# SANE_v2.net
KiCad netlist of a schematic drawn in EAGLE
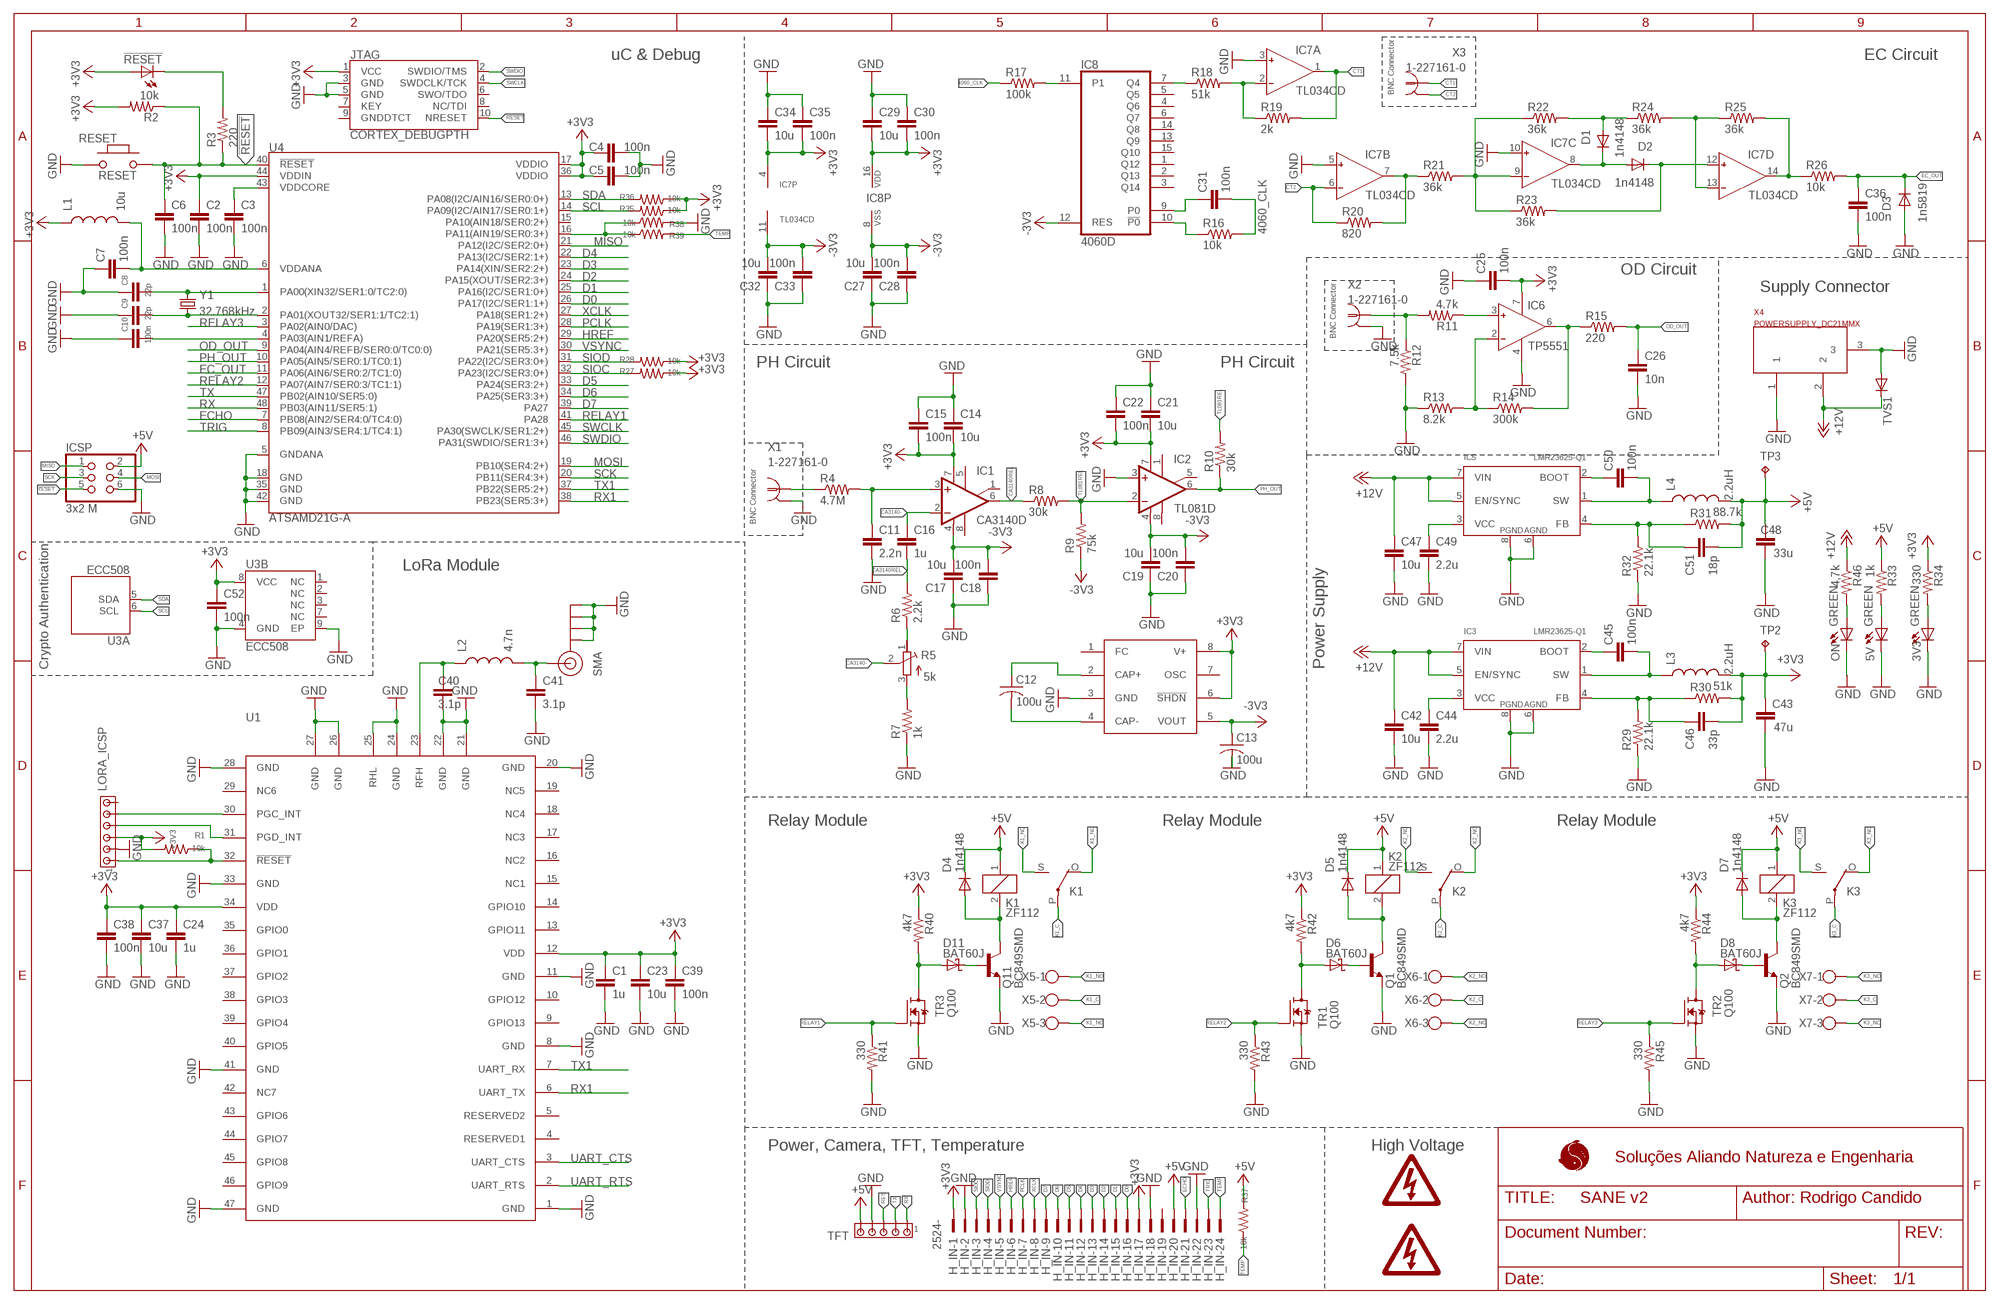
[diagram p0: schematic, sheet 1]

(export (version "E")
  (design (tool "Eeschema 10.0.6"))
  (components
    (comp (ref "!RESET")
      (value "LEDCHIPLED_0805")
      (footprint "eagle-import:CHIPLED_0805")
      (libsource (lib "eagle-import") (part "LEDCHIPLED_0805"))
    )
    (comp (ref "3V3")
      (value "GREEN")
      (footprint "eagle-import:CHIP-LED0805")
      (libsource (lib "eagle-import") (part "LEDCHIP-LED0805"))
    )
    (comp (ref "5V")
      (value "GREEN")
      (footprint "eagle-import:CHIP-LED0805")
      (libsource (lib "eagle-import") (part "LEDCHIP-LED0805"))
    )
    (comp (ref "C1")
      (value "1u")
      (footprint "eagle-import:C1206")
      (libsource (lib "eagle-import") (part "C-EUC1206"))
    )
    (comp (ref "C2")
      (value "100n")
      (footprint "eagle-import:C0805")
      (libsource (lib "eagle-import") (part "C-EUC0805"))
    )
    (comp (ref "C3")
      (value "100n")
      (footprint "eagle-import:C0805")
      (libsource (lib "eagle-import") (part "C-EUC0805"))
    )
    (comp (ref "C4")
      (value "100n")
      (footprint "eagle-import:C0805")
      (libsource (lib "eagle-import") (part "C-EUC0805"))
    )
    (comp (ref "C5")
      (value "100n")
      (footprint "eagle-import:C0805")
      (libsource (lib "eagle-import") (part "C-EUC0805"))
    )
    (comp (ref "C6")
      (value "100n")
      (footprint "eagle-import:C0805")
      (libsource (lib "eagle-import") (part "C-EUC0805"))
    )
    (comp (ref "C7")
      (value "100n")
      (footprint "eagle-import:C0805")
      (libsource (lib "eagle-import") (part "C-EUC0805"))
    )
    (comp (ref "C8")
      (value "22p")
      (footprint "eagle-import:C0805")
      (libsource (lib "eagle-import") (part "C-EUC0805"))
    )
    (comp (ref "C9")
      (value "22p")
      (footprint "eagle-import:C0805")
      (libsource (lib "eagle-import") (part "C-EUC0805"))
    )
    (comp (ref "C10")
      (value "100n")
      (footprint "eagle-import:C0805")
      (libsource (lib "eagle-import") (part "C-EUC0805"))
    )
    (comp (ref "C11")
      (value "2.2n")
      (footprint "eagle-import:C0805")
      (libsource (lib "eagle-import") (part "C-EUC0805"))
    )
    (comp (ref "C12")
      (value "100u")
      (footprint "eagle-import:C1206")
      (libsource (lib "eagle-import") (part "C-USC1206"))
    )
    (comp (ref "C13")
      (value "100u")
      (footprint "eagle-import:C1206")
      (libsource (lib "eagle-import") (part "C-USC1206"))
    )
    (comp (ref "C14")
      (value "10u")
      (footprint "eagle-import:C1206")
      (libsource (lib "eagle-import") (part "C-EUC1206"))
    )
    (comp (ref "C15")
      (value "100n")
      (footprint "eagle-import:C0805")
      (libsource (lib "eagle-import") (part "C-EUC0805"))
    )
    (comp (ref "C16")
      (value "1u")
      (footprint "eagle-import:C1206")
      (libsource (lib "eagle-import") (part "C-EUC1206"))
    )
    (comp (ref "C17")
      (value "10u")
      (footprint "eagle-import:C1206")
      (libsource (lib "eagle-import") (part "C-EUC1206"))
    )
    (comp (ref "C18")
      (value "100n")
      (footprint "eagle-import:C0805")
      (libsource (lib "eagle-import") (part "C-EUC0805"))
    )
    (comp (ref "C19")
      (value "10u")
      (footprint "eagle-import:C1206")
      (libsource (lib "eagle-import") (part "C-EUC1206"))
    )
    (comp (ref "C20")
      (value "100n")
      (footprint "eagle-import:C0805")
      (libsource (lib "eagle-import") (part "C-EUC0805"))
    )
    (comp (ref "C21")
      (value "10u")
      (footprint "eagle-import:C1206")
      (libsource (lib "eagle-import") (part "C-EUC1206"))
    )
    (comp (ref "C22")
      (value "100n")
      (footprint "eagle-import:C0805")
      (libsource (lib "eagle-import") (part "C-EUC0805"))
    )
    (comp (ref "C23")
      (value "10u")
      (footprint "eagle-import:C1206")
      (libsource (lib "eagle-import") (part "C-EUC1206"))
    )
    (comp (ref "C24")
      (value "1u")
      (footprint "eagle-import:C1206")
      (libsource (lib "eagle-import") (part "C-EUC1206"))
    )
    (comp (ref "C25")
      (value "100n")
      (footprint "eagle-import:C0805")
      (libsource (lib "eagle-import") (part "C-EUC0805"))
    )
    (comp (ref "C26")
      (value "10n")
      (footprint "eagle-import:C0805")
      (libsource (lib "eagle-import") (part "C-EUC0805"))
    )
    (comp (ref "C27")
      (value "10u")
      (footprint "eagle-import:C1206")
      (libsource (lib "eagle-import") (part "C-EUC1206"))
    )
    (comp (ref "C28")
      (value "100n")
      (footprint "eagle-import:C0805")
      (libsource (lib "eagle-import") (part "C-EUC0805"))
    )
    (comp (ref "C29")
      (value "10u")
      (footprint "eagle-import:C1206")
      (libsource (lib "eagle-import") (part "C-EUC1206"))
    )
    (comp (ref "C30")
      (value "100n")
      (footprint "eagle-import:C0805")
      (libsource (lib "eagle-import") (part "C-EUC0805"))
    )
    (comp (ref "C31")
      (value "100n")
      (footprint "eagle-import:C0805")
      (libsource (lib "eagle-import") (part "C-EUC0805"))
    )
    (comp (ref "C32")
      (value "10u")
      (footprint "eagle-import:C1206")
      (libsource (lib "eagle-import") (part "C-EUC1206"))
    )
    (comp (ref "C33")
      (value "100n")
      (footprint "eagle-import:C0805")
      (libsource (lib "eagle-import") (part "C-EUC0805"))
    )
    (comp (ref "C34")
      (value "10u")
      (footprint "eagle-import:C1206")
      (libsource (lib "eagle-import") (part "C-EUC1206"))
    )
    (comp (ref "C35")
      (value "100n")
      (footprint "eagle-import:C0805")
      (libsource (lib "eagle-import") (part "C-EUC0805"))
    )
    (comp (ref "C36")
      (value "100n")
      (footprint "eagle-import:C0805")
      (libsource (lib "eagle-import") (part "C-EUC0805"))
    )
    (comp (ref "C37")
      (value "10u")
      (footprint "eagle-import:C1206")
      (libsource (lib "eagle-import") (part "C-EUC1206"))
    )
    (comp (ref "C38")
      (value "100n")
      (footprint "eagle-import:C0805")
      (libsource (lib "eagle-import") (part "C-EUC0805"))
    )
    (comp (ref "C39")
      (value "100n")
      (footprint "eagle-import:C0805")
      (libsource (lib "eagle-import") (part "C-EUC0805"))
    )
    (comp (ref "C40")
      (value "3.1p")
      (footprint "eagle-import:C0603")
      (libsource (lib "eagle-import") (part "C-EUC0603"))
    )
    (comp (ref "C41")
      (value "3.1p")
      (footprint "eagle-import:C0603")
      (libsource (lib "eagle-import") (part "C-EUC0603"))
    )
    (comp (ref "C42")
      (value "10u")
      (footprint "eagle-import:C1206")
      (libsource (lib "eagle-import") (part "C-EUC1206"))
    )
    (comp (ref "C43")
      (value "47u")
      (footprint "eagle-import:C1206")
      (libsource (lib "eagle-import") (part "C-EUC1206"))
    )
    (comp (ref "C44")
      (value "2.2u")
      (footprint "eagle-import:C0805")
      (libsource (lib "eagle-import") (part "C-EUC0805"))
    )
    (comp (ref "C45")
      (value "100n")
      (footprint "eagle-import:C0805")
      (libsource (lib "eagle-import") (part "C-EUC0805"))
    )
    (comp (ref "C46")
      (value "33p")
      (footprint "eagle-import:C0805")
      (libsource (lib "eagle-import") (part "C-EUC0805"))
    )
    (comp (ref "C47")
      (value "10u")
      (footprint "eagle-import:C1206")
      (libsource (lib "eagle-import") (part "C-EUC1206"))
    )
    (comp (ref "C48")
      (value "33u")
      (footprint "eagle-import:C1206")
      (libsource (lib "eagle-import") (part "C-EUC1206"))
    )
    (comp (ref "C49")
      (value "2.2u")
      (footprint "eagle-import:C0805")
      (libsource (lib "eagle-import") (part "C-EUC0805"))
    )
    (comp (ref "C50")
      (value "100n")
      (footprint "eagle-import:C0805")
      (libsource (lib "eagle-import") (part "C-EUC0805"))
    )
    (comp (ref "C51")
      (value "18p")
      (footprint "eagle-import:C0805")
      (libsource (lib "eagle-import") (part "C-EUC0805"))
    )
    (comp (ref "C52")
      (value "100n")
      (footprint "eagle-import:C0805")
      (libsource (lib "eagle-import") (part "C-EUC0805"))
    )
    (comp (ref "D1")
      (value "1n4148")
      (footprint "eagle-import:SOD123")
      (libsource (lib "eagle-import") (part "DIODE-SOD123"))
    )
    (comp (ref "D2")
      (value "1n4148")
      (footprint "eagle-import:SOD123")
      (libsource (lib "eagle-import") (part "DIODE-SOD123"))
    )
    (comp (ref "D3")
      (value "1n5819")
      (footprint "eagle-import:SOD123")
      (libsource (lib "eagle-import") (part "DIODE-SOD123"))
    )
    (comp (ref "D4")
      (value "1n4148")
      (footprint "eagle-import:SOD123")
      (libsource (lib "eagle-import") (part "DIODE-SOD123"))
    )
    (comp (ref "D5")
      (value "1n4148")
      (footprint "eagle-import:SOD123")
      (libsource (lib "eagle-import") (part "DIODE-SOD123"))
    )
    (comp (ref "D6")
      (value "BAT60J")
      (footprint "eagle-import:SOD323_ST")
      (libsource (lib "eagle-import") (part "BAT60J"))
    )
    (comp (ref "D7")
      (value "1n4148")
      (footprint "eagle-import:SOD123")
      (libsource (lib "eagle-import") (part "DIODE-SOD123"))
    )
    (comp (ref "D8")
      (value "BAT60J")
      (footprint "eagle-import:SOD323_ST")
      (libsource (lib "eagle-import") (part "BAT60J"))
    )
    (comp (ref "D11")
      (value "BAT60J")
      (footprint "eagle-import:SOD323_ST")
      (libsource (lib "eagle-import") (part "BAT60J"))
    )
    (comp (ref "H_IN")
      (value "2524-")
      (footprint "eagle-import:PAK100_2500-24")
      (libsource (lib "eagle-import") (part "2524-"))
    )
    (comp (ref "IC1")
      (value "CA3140D")
      (footprint "eagle-import:SO08")
      (libsource (lib "eagle-import") (part "CA3140D"))
    )
    (comp (ref "IC2")
      (value "TL081D")
      (footprint "eagle-import:SO08")
      (libsource (lib "eagle-import") (part "TL081D"))
    )
    (comp (ref "IC3")
      (value "LMR23625-Q1")
      (footprint "eagle-import:SO08")
      (fields (field (name "MF") "Texas Instruments"))
      (libsource (lib "eagle-import") (part "LMR23625-Q1"))
    )
    (comp (ref "IC4")
      (value "TC1121COA")
      (footprint "eagle-import:SO8")
      (libsource (lib "eagle-import") (part "TC1121COA"))
    )
    (comp (ref "IC5")
      (value "LMR23625-Q1")
      (footprint "eagle-import:SO08")
      (fields (field (name "MF") "Texas Instruments"))
      (libsource (lib "eagle-import") (part "LMR23625-Q1"))
    )
    (comp (ref "IC6")
      (value "TP5551")
      (footprint "eagle-import:SO8")
      (libsource (lib "eagle-import") (part "TP5551"))
    )
    (comp (ref "IC7")
      (value "TL034CD")
      (footprint "eagle-import:SO14")
      (libsource (lib "eagle-import") (part "TL034CD"))
    )
    (comp (ref "IC8")
      (value "4060D")
      (footprint "eagle-import:SO16")
      (libsource (lib "eagle-import") (part "4060D"))
    )
    (comp (ref "ICSP")
      (value "3x2 M")
      (footprint "eagle-import:2X03")
      (libsource (lib "eagle-import") (part "ICSP"))
    )
    (comp (ref "JTAG")
      (value "CORTEX_DEBUGPTH")
      (footprint "eagle-import:2X5-PTH-1.27MM")
      (libsource (lib "eagle-import") (part "CORTEX_DEBUGPTH"))
    )
    (comp (ref "K1")
      (value "ZF112")
      (footprint "eagle-import:ZF112")
      (libsource (lib "eagle-import") (part "ZF112"))
    )
    (comp (ref "K2")
      (value "ZF112")
      (footprint "eagle-import:ZF112")
      (libsource (lib "eagle-import") (part "ZF112"))
    )
    (comp (ref "K3")
      (value "ZF112")
      (footprint "eagle-import:ZF112")
      (libsource (lib "eagle-import") (part "ZF112"))
    )
    (comp (ref "L1")
      (value "10u")
      (footprint "eagle-import:0603")
      (libsource (lib "eagle-import") (part "INDUCTOR0603"))
    )
    (comp (ref "L2")
      (value "4.7n")
      (footprint "eagle-import:0603")
      (libsource (lib "eagle-import") (part "INDUCTOR0603"))
    )
    (comp (ref "L3")
      (value "2.2uH")
      (footprint "eagle-import:L-NR3010")
      (libsource (lib "eagle-import") (part "L-NR3010"))
    )
    (comp (ref "L4")
      (value "2.2uH")
      (footprint "eagle-import:L-NR3010")
      (libsource (lib "eagle-import") (part "L-NR3010"))
    )
    (comp (ref "LORA_ICSP")
      (value "MTA06-100")
      (footprint "eagle-import:10X06MTA")
      (libsource (lib "eagle-import") (part "MTA06-100"))
    )
    (comp (ref "ON")
      (value "GREEN")
      (footprint "eagle-import:CHIP-LED0805")
      (libsource (lib "eagle-import") (part "LEDCHIP-LED0805"))
    )
    (comp (ref "Q1")
      (value "BC849SMD")
      (footprint "eagle-import:SOT23-BEC")
      (libsource (lib "eagle-import") (part "BC849SMD"))
    )
    (comp (ref "Q2")
      (value "BC849SMD")
      (footprint "eagle-import:SOT23-BEC")
      (libsource (lib "eagle-import") (part "BC849SMD"))
    )
    (comp (ref "Q11")
      (value "BC849SMD")
      (footprint "eagle-import:SOT23-BEC")
      (libsource (lib "eagle-import") (part "BC849SMD"))
    )
    (comp (ref "R1")
      (value "10k")
      (footprint "eagle-import:R0805")
      (libsource (lib "eagle-import") (part "R-US_R0805"))
    )
    (comp (ref "R2")
      (value "10k")
      (footprint "eagle-import:R0805")
      (libsource (lib "eagle-import") (part "R-US_R0805"))
    )
    (comp (ref "R3")
      (value "220")
      (footprint "eagle-import:R0805")
      (libsource (lib "eagle-import") (part "R-US_R0805"))
    )
    (comp (ref "R4")
      (value "4.7M")
      (footprint "eagle-import:R0805")
      (libsource (lib "eagle-import") (part "R-US_R0805"))
    )
    (comp (ref "R5")
      (value "5k")
      (footprint "eagle-import:RTRIMT93YA")
      (libsource (lib "eagle-import") (part "R-TRIMMT93YA"))
    )
    (comp (ref "R6")
      (value "2.2k")
      (footprint "eagle-import:R0805")
      (libsource (lib "eagle-import") (part "R-US_R0805"))
    )
    (comp (ref "R7")
      (value "1k")
      (footprint "eagle-import:R0805")
      (libsource (lib "eagle-import") (part "R-US_R0805"))
    )
    (comp (ref "R8")
      (value "30k")
      (footprint "eagle-import:R0805")
      (libsource (lib "eagle-import") (part "R-US_R0805"))
    )
    (comp (ref "R9")
      (value "75k")
      (footprint "eagle-import:R0805")
      (libsource (lib "eagle-import") (part "R-US_R0805"))
    )
    (comp (ref "R10")
      (value "30k")
      (footprint "eagle-import:R0805")
      (libsource (lib "eagle-import") (part "R-US_R0805"))
    )
    (comp (ref "R11")
      (value "4.7k")
      (footprint "eagle-import:R0805")
      (libsource (lib "eagle-import") (part "R-US_R0805"))
    )
    (comp (ref "R12")
      (value "7.5k")
      (footprint "eagle-import:R0805")
      (libsource (lib "eagle-import") (part "R-US_R0805"))
    )
    (comp (ref "R13")
      (value "8.2k")
      (footprint "eagle-import:R0805")
      (libsource (lib "eagle-import") (part "R-US_R0805"))
    )
    (comp (ref "R14")
      (value "300k")
      (footprint "eagle-import:R0805")
      (libsource (lib "eagle-import") (part "R-US_R0805"))
    )
    (comp (ref "R15")
      (value "220")
      (footprint "eagle-import:R0805")
      (libsource (lib "eagle-import") (part "R-US_R0805"))
    )
    (comp (ref "R16")
      (value "10k")
      (footprint "eagle-import:R0805")
      (libsource (lib "eagle-import") (part "R-US_R0805"))
    )
    (comp (ref "R17")
      (value "100k")
      (footprint "eagle-import:R0805")
      (libsource (lib "eagle-import") (part "R-US_R0805"))
    )
    (comp (ref "R18")
      (value "51k")
      (footprint "eagle-import:R0805")
      (libsource (lib "eagle-import") (part "R-US_R0805"))
    )
    (comp (ref "R19")
      (value "2k")
      (footprint "eagle-import:R0805")
      (libsource (lib "eagle-import") (part "R-US_R0805"))
    )
    (comp (ref "R20")
      (value "820")
      (footprint "eagle-import:R0805")
      (libsource (lib "eagle-import") (part "R-US_R0805"))
    )
    (comp (ref "R21")
      (value "36k")
      (footprint "eagle-import:R0805")
      (libsource (lib "eagle-import") (part "R-US_R0805"))
    )
    (comp (ref "R22")
      (value "36k")
      (footprint "eagle-import:R0805")
      (libsource (lib "eagle-import") (part "R-US_R0805"))
    )
    (comp (ref "R23")
      (value "36k")
      (footprint "eagle-import:R0805")
      (libsource (lib "eagle-import") (part "R-US_R0805"))
    )
    (comp (ref "R24")
      (value "36k")
      (footprint "eagle-import:R0805")
      (libsource (lib "eagle-import") (part "R-US_R0805"))
    )
    (comp (ref "R25")
      (value "36k")
      (footprint "eagle-import:R0805")
      (libsource (lib "eagle-import") (part "R-US_R0805"))
    )
    (comp (ref "R26")
      (value "10k")
      (footprint "eagle-import:R0805")
      (libsource (lib "eagle-import") (part "R-US_R0805"))
    )
    (comp (ref "R27")
      (value "10k")
      (footprint "eagle-import:R0805")
      (libsource (lib "eagle-import") (part "R-US_R0805"))
    )
    (comp (ref "R28")
      (value "10k")
      (footprint "eagle-import:R0805")
      (libsource (lib "eagle-import") (part "R-US_R0805"))
    )
    (comp (ref "R29")
      (value "22.1k")
      (footprint "eagle-import:R0603")
      (libsource (lib "eagle-import") (part "R-US_R0603"))
    )
    (comp (ref "R30")
      (value "51k")
      (footprint "eagle-import:R0603")
      (libsource (lib "eagle-import") (part "R-US_R0603"))
    )
    (comp (ref "R31")
      (value "88.7k")
      (footprint "eagle-import:R0603")
      (libsource (lib "eagle-import") (part "R-US_R0603"))
    )
    (comp (ref "R32")
      (value "22.1k")
      (footprint "eagle-import:R0603")
      (libsource (lib "eagle-import") (part "R-US_R0603"))
    )
    (comp (ref "R33")
      (value "1k")
      (footprint "eagle-import:R0805")
      (libsource (lib "eagle-import") (part "resistor_R-US_R0805"))
    )
    (comp (ref "R34")
      (value "330")
      (footprint "eagle-import:R0805")
      (libsource (lib "eagle-import") (part "resistor_R-US_R0805"))
    )
    (comp (ref "R35")
      (value "10k")
      (footprint "eagle-import:R0805")
      (libsource (lib "eagle-import") (part "R-US_R0805"))
    )
    (comp (ref "R36")
      (value "10k")
      (footprint "eagle-import:R0805")
      (libsource (lib "eagle-import") (part "R-US_R0805"))
    )
    (comp (ref "R37")
      (value "10k")
      (footprint "eagle-import:R0805")
      (libsource (lib "eagle-import") (part "R-US_R0805"))
    )
    (comp (ref "R38")
      (value "10k")
      (footprint "eagle-import:R0805")
      (libsource (lib "eagle-import") (part "R-US_R0805"))
    )
    (comp (ref "R39")
      (value "10k")
      (footprint "eagle-import:R0805")
      (libsource (lib "eagle-import") (part "R-US_R0805"))
    )
    (comp (ref "R40")
      (value "4k7")
      (footprint "eagle-import:R0805")
      (libsource (lib "eagle-import") (part "R-US_R0805"))
    )
    (comp (ref "R41")
      (value "330")
      (footprint "eagle-import:R0805")
      (libsource (lib "eagle-import") (part "R-US_R0805"))
    )
    (comp (ref "R42")
      (value "4k7")
      (footprint "eagle-import:R0805")
      (libsource (lib "eagle-import") (part "R-US_R0805"))
    )
    (comp (ref "R43")
      (value "330")
      (footprint "eagle-import:R0805")
      (libsource (lib "eagle-import") (part "R-US_R0805"))
    )
    (comp (ref "R44")
      (value "4k7")
      (footprint "eagle-import:R0805")
      (libsource (lib "eagle-import") (part "R-US_R0805"))
    )
    (comp (ref "R45")
      (value "330")
      (footprint "eagle-import:R0805")
      (libsource (lib "eagle-import") (part "R-US_R0805"))
    )
    (comp (ref "R46")
      (value "4,7k")
      (footprint "eagle-import:R0805")
      (libsource (lib "eagle-import") (part "resistor_R-US_R0805"))
    )
    (comp (ref "RESET")
      (value "RESET")
      (footprint "eagle-import:SMD_157SW")
      (fields (field (name "PART_NUMBER") "IT-1185AP1C-160G-G_T&R"))
      (libsource (lib "eagle-import") (part "0173_IT-1185AP1C-160G-G_T&R"))
    )
    (comp (ref "SMA_GPS")
      (value "SMA_EDGE")
      (footprint "eagle-import:SMA-EDGE")
      (libsource (lib "eagle-import") (part "SMA_EDGE"))
    )
    (comp (ref "TFT")
      (value "MTA05-100")
      (footprint "eagle-import:10X05MTA")
      (libsource (lib "eagle-import") (part "MTA05-100"))
    )
    (comp (ref "TP2")
      (value "TPPAD1-13")
      (footprint "eagle-import:P1-13")
      (libsource (lib "eagle-import") (part "TPPAD1-13"))
    )
    (comp (ref "TP3")
      (value "TPPAD1-13")
      (footprint "eagle-import:P1-13")
      (libsource (lib "eagle-import") (part "TPPAD1-13"))
    )
    (comp (ref "TR1")
      (value "Q100")
      (footprint "eagle-import:SOT-23")
      (libsource (lib "eagle-import") (part "1612_2N7002LT1G"))
    )
    (comp (ref "TR2")
      (value "Q100")
      (footprint "eagle-import:SOT-23")
      (libsource (lib "eagle-import") (part "1612_2N7002LT1G"))
    )
    (comp (ref "TR3")
      (value "Q100")
      (footprint "eagle-import:SOT-23")
      (libsource (lib "eagle-import") (part "1612_2N7002LT1G"))
    )
    (comp (ref "TVS1")
      (value "DIODE-SOD123")
      (footprint "eagle-import:SOD123")
      (libsource (lib "eagle-import") (part "DIODE-SOD123"))
    )
    (comp (ref "U$1")
      (value "SHOCK")
      (footprint "eagle-import:SHOCK")
      (libsource (lib "eagle-import") (part "SHOCK"))
    )
    (comp (ref "U$2")
      (value "SHOCK")
      (footprint "eagle-import:SHOCK")
      (libsource (lib "eagle-import") (part "SHOCK"))
    )
    (comp (ref "U$3")
      (value "LOGO-SANE")
      (footprint "eagle-import:LOGO-SANE")
      (libsource (lib "eagle-import") (part "LOGO-SANE"))
    )
    (comp (ref "U$9")
      (value "SHOCK")
      (footprint "eagle-import:SHOCK")
      (libsource (lib "eagle-import") (part "SHOCK"))
    )
    (comp (ref "U1")
      (value "RN2483/RN2903")
      (footprint "eagle-import:RN2483_RN2903")
      (libsource (lib "eagle-import") (part "RN2483/RN2903"))
    )
    (comp (ref "U3")
      (value "ECC508")
      (footprint "eagle-import:SON50P300X200X60-9N-EP160X140")
      (fields (field (name "MANUFACTURER") "Atmel"))
      (libsource (lib "eagle-import") (part "ATECC508A-MAHDA-T8-UDFN"))
    )
    (comp (ref "U4")
      (value "ATSAMD21G-A")
      (footprint "eagle-import:TQFP-48")
      (libsource (lib "eagle-import") (part "ATSAMD21G-A"))
    )
    (comp (ref "X1")
      (value "1-227161-0")
      (footprint "eagle-import:AMP_227161")
      (fields (field (name "MF") "TYCO ELECTRONICS") (field (name "MPN") "1-227161"))
      (libsource (lib "eagle-import") (part "?2271611--0"))
    )
    (comp (ref "X2")
      (value "1-227161-0")
      (footprint "eagle-import:AMP_227161")
      (fields (field (name "MF") "TYCO ELECTRONICS") (field (name "MPN") "1-227161"))
      (libsource (lib "eagle-import") (part "?2271611--0"))
    )
    (comp (ref "X3")
      (value "1-227161-0")
      (footprint "eagle-import:AMP_227161")
      (fields (field (name "MF") "TYCO ELECTRONICS") (field (name "MPN") "1-227161"))
      (libsource (lib "eagle-import") (part "?2271611--0"))
    )
    (comp (ref "X4")
      (value "POWERSUPPLY_DC21MMX")
      (footprint "eagle-import:POWERSUPPLY_DC-21MM")
      (libsource (lib "eagle-import") (part "POWERSUPPLY_DC21MMX"))
    )
    (comp (ref "X5")
      (value "W237-103")
      (footprint "eagle-import:W237-103")
      (fields (field (name "MPN") "237-103"))
      (libsource (lib "eagle-import") (part "W237-103"))
    )
    (comp (ref "X6")
      (value "W237-103")
      (footprint "eagle-import:W237-103")
      (fields (field (name "MPN") "237-103"))
      (libsource (lib "eagle-import") (part "W237-103"))
    )
    (comp (ref "X7")
      (value "W237-103")
      (footprint "eagle-import:W237-103")
      (fields (field (name "MPN") "237-103"))
      (libsource (lib "eagle-import") (part "W237-103"))
    )
    (comp (ref "Y1")
      (value "32.768kHz")
      (footprint "eagle-import:CRYSTAL-SMD-3.2X1.5MM")
      (libsource (lib "eagle-import") (part "CRYSTAL3.2X1.5MM"))
    )
  )
  (nets
    (net (code "1") (name "+3V3") (class "Default")
      (node (ref "!RESET") (pin "A") (pinfunction "A_A") (pintype "passive"))
      (node (ref "C1") (pin "1") (pinfunction "1_1") (pintype "passive"))
      (node (ref "C14") (pin "2") (pinfunction "2_2") (pintype "passive"))
      (node (ref "C15") (pin "2") (pinfunction "2_2") (pintype "passive"))
      (node (ref "C2") (pin "1") (pinfunction "1_1") (pintype "passive"))
      (node (ref "C21") (pin "2") (pinfunction "2_2") (pintype "passive"))
      (node (ref "C22") (pin "2") (pinfunction "2_2") (pintype "passive"))
      (node (ref "C23") (pin "1") (pinfunction "1_1") (pintype "passive"))
      (node (ref "C24") (pin "1") (pinfunction "1_1") (pintype "passive"))
      (node (ref "C25") (pin "2") (pinfunction "2_2") (pintype "passive"))
      (node (ref "C29") (pin "2") (pinfunction "2_2") (pintype "passive"))
      (node (ref "C30") (pin "2") (pinfunction "2_2") (pintype "passive"))
      (node (ref "C34") (pin "2") (pinfunction "2_2") (pintype "passive"))
      (node (ref "C35") (pin "2") (pinfunction "2_2") (pintype "passive"))
      (node (ref "C37") (pin "1") (pinfunction "1_1") (pintype "passive"))
      (node (ref "C38") (pin "1") (pinfunction "1_1") (pintype "passive"))
      (node (ref "C39") (pin "1") (pinfunction "1_1") (pintype "passive"))
      (node (ref "C4") (pin "1") (pinfunction "1_1") (pintype "passive"))
      (node (ref "C43") (pin "2") (pinfunction "2_2") (pintype "passive"))
      (node (ref "C46") (pin "2") (pinfunction "2_2") (pintype "passive"))
      (node (ref "C5") (pin "1") (pinfunction "1_1") (pintype "passive"))
      (node (ref "C52") (pin "1") (pinfunction "1_1") (pintype "passive"))
      (node (ref "H_IN") (pin "1") (pinfunction "KL_1") (pintype "passive"))
      (node (ref "H_IN") (pin "17") (pinfunction "KL_17") (pintype "passive"))
      (node (ref "IC1") (pin "7") (pinfunction "V+_7") (pintype "power_in"))
      (node (ref "IC2") (pin "7") (pinfunction "V+_7") (pintype "power_in"))
      (node (ref "IC4") (pin "6") (pinfunction "~{SHDN}_6") (pintype "passive"))
      (node (ref "IC4") (pin "8") (pinfunction "V+_8") (pintype "power_in"))
      (node (ref "IC6") (pin "7") (pinfunction "V+_7") (pintype "power_in"))
      (node (ref "IC7") (pin "4") (pinfunction "V+_4") (pintype "power_in"))
      (node (ref "IC8") (pin "16") (pinfunction "VDD_16") (pintype "power_in"))
      (node (ref "JTAG") (pin "1") (pinfunction "VCC_1") (pintype "bidirectional"))
      (node (ref "L1") (pin "1") (pinfunction "1_1") (pintype "passive"))
      (node (ref "L3") (pin "P$2") (pinfunction "2_P$2") (pintype "passive"))
      (node (ref "LORA_ICSP") (pin "3") (pinfunction "3_3") (pintype "passive"))
      (node (ref "R1") (pin "2") (pinfunction "2_2") (pintype "passive"))
      (node (ref "R2") (pin "2") (pinfunction "2_2") (pintype "passive"))
      (node (ref "R27") (pin "1") (pinfunction "1_1") (pintype "passive"))
      (node (ref "R28") (pin "1") (pinfunction "1_1") (pintype "passive"))
      (node (ref "R30") (pin "2") (pinfunction "2_2") (pintype "passive"))
      (node (ref "R34") (pin "1") (pinfunction "1_1") (pintype "passive"))
      (node (ref "R35") (pin "1") (pinfunction "1_1") (pintype "passive"))
      (node (ref "R36") (pin "1") (pinfunction "1_1") (pintype "passive"))
      (node (ref "R40") (pin "1") (pinfunction "1_1") (pintype "passive"))
      (node (ref "R42") (pin "1") (pinfunction "1_1") (pintype "passive"))
      (node (ref "R44") (pin "1") (pinfunction "1_1") (pintype "passive"))
      (node (ref "TP2") (pin "TP") (pinfunction "TP_TP") (pintype "input"))
      (node (ref "U1") (pin "12") (pinfunction "VDD_12") (pintype "bidirectional"))
      (node (ref "U1") (pin "34") (pinfunction "VDD_34") (pintype "bidirectional"))
      (node (ref "U3") (pin "8") (pinfunction "VCC_8") (pintype "power_in"))
      (node (ref "U4") (pin "17") (pinfunction "VDDIO_17") (pintype "bidirectional"))
      (node (ref "U4") (pin "36") (pinfunction "VDDIO_36") (pintype "bidirectional"))
      (node (ref "U4") (pin "44") (pinfunction "VDDIN_44") (pintype "bidirectional"))
    )
    (net (code "2") (name "+5V") (class "Default")
      (node (ref "C48") (pin "2") (pinfunction "2_2") (pintype "passive"))
      (node (ref "C51") (pin "2") (pinfunction "2_2") (pintype "passive"))
      (node (ref "D4") (pin "C") (pinfunction "C_C") (pintype "passive"))
      (node (ref "D5") (pin "C") (pinfunction "C_C") (pintype "passive"))
      (node (ref "D7") (pin "C") (pinfunction "C_C") (pintype "passive"))
      (node (ref "H_IN") (pin "20") (pinfunction "KL_20") (pintype "passive"))
      (node (ref "ICSP") (pin "2") (pinfunction "2_2") (pintype "passive"))
      (node (ref "K1") (pin "1") (pinfunction "1_1") (pintype "passive"))
      (node (ref "K2") (pin "1") (pinfunction "1_1") (pintype "passive"))
      (node (ref "K3") (pin "1") (pinfunction "1_1") (pintype "passive"))
      (node (ref "L4") (pin "P$2") (pinfunction "2_P$2") (pintype "passive"))
      (node (ref "R31") (pin "2") (pinfunction "2_2") (pintype "passive"))
      (node (ref "R33") (pin "1") (pinfunction "1_1") (pintype "passive"))
      (node (ref "R37") (pin "2") (pinfunction "2_2") (pintype "passive"))
      (node (ref "TFT") (pin "5") (pinfunction "5_5") (pintype "passive"))
      (node (ref "TP3") (pin "TP") (pinfunction "TP_TP") (pintype "input"))
    )
    (net (code "3") (name "+12V") (class "Default")
      (node (ref "C42") (pin "1") (pinfunction "1_1") (pintype "passive"))
      (node (ref "C47") (pin "1") (pinfunction "1_1") (pintype "passive"))
      (node (ref "IC3") (pin "5") (pinfunction "EN/SYNC_5") (pintype "bidirectional"))
      (node (ref "IC3") (pin "7") (pinfunction "VIN_7") (pintype "bidirectional"))
      (node (ref "IC5") (pin "5") (pinfunction "EN/SYNC_5") (pintype "bidirectional"))
      (node (ref "IC5") (pin "7") (pinfunction "VIN_7") (pintype "bidirectional"))
      (node (ref "R46") (pin "1") (pinfunction "1_1") (pintype "passive"))
      (node (ref "TVS1") (pin "C") (pinfunction "C_C") (pintype "passive"))
      (node (ref "X4") (pin "2") (pinfunction "2_2") (pintype "power_in"))
    )
    (net (code "4") (name "-3V3") (class "Default")
      (node (ref "C13") (pin "1") (pinfunction "1_1") (pintype "passive"))
      (node (ref "C17") (pin "2") (pinfunction "2_2") (pintype "passive"))
      (node (ref "C18") (pin "2") (pinfunction "2_2") (pintype "passive"))
      (node (ref "C19") (pin "2") (pinfunction "2_2") (pintype "passive"))
      (node (ref "C20") (pin "2") (pinfunction "2_2") (pintype "passive"))
      (node (ref "C27") (pin "2") (pinfunction "2_2") (pintype "passive"))
      (node (ref "C28") (pin "2") (pinfunction "2_2") (pintype "passive"))
      (node (ref "C32") (pin "2") (pinfunction "2_2") (pintype "passive"))
      (node (ref "C33") (pin "2") (pinfunction "2_2") (pintype "passive"))
      (node (ref "IC1") (pin "4") (pinfunction "V-_4") (pintype "power_in"))
      (node (ref "IC2") (pin "4") (pinfunction "V-_4") (pintype "power_in"))
      (node (ref "IC4") (pin "5") (pinfunction "VOUT_5") (pintype "output"))
      (node (ref "IC7") (pin "11") (pinfunction "V-_11") (pintype "power_in"))
      (node (ref "IC8") (pin "12") (pinfunction "RES_12") (pintype "input"))
      (node (ref "IC8") (pin "8") (pinfunction "VSS_8") (pintype "power_in"))
      (node (ref "R9") (pin "1") (pinfunction "1_1") (pintype "passive"))
    )
    (net (code "5") (name "/RX1") (class "Default")
      (node (ref "U1") (pin "6") (pinfunction "UART_TX_6") (pintype "bidirectional"))
      (node (ref "U4") (pin "38") (pinfunction "PB23(SER5:3+)_38") (pintype "bidirectional"))
    )
    (net (code "6") (name "/TX1") (class "Default")
      (node (ref "U1") (pin "7") (pinfunction "UART_RX_7") (pintype "bidirectional"))
      (node (ref "U4") (pin "37") (pinfunction "PB22(SER5:2+)_37") (pintype "bidirectional"))
    )
    (net (code "7") (name "/UART_CTS") (class "Default")
      (node (ref "U1") (pin "3") (pinfunction "UART_CTS_3") (pintype "bidirectional"))
    )
    (net (code "8") (name "/UART_RTS") (class "Default")
      (node (ref "U1") (pin "2") (pinfunction "UART_RTS_2") (pintype "bidirectional"))
    )
    (net (code "9") (name "/~{RESET}") (class "Default")
      (node (ref "C6") (pin "1") (pinfunction "1_1") (pintype "passive"))
      (node (ref "ICSP") (pin "5") (pinfunction "5_5") (pintype "passive"))
      (node (ref "JTAG") (pin "10") (pinfunction "NRESET_10") (pintype "bidirectional"))
      (node (ref "R2") (pin "1") (pinfunction "1_1") (pintype "passive"))
      (node (ref "R3") (pin "1") (pinfunction "1_1") (pintype "passive"))
      (node (ref "RESET") (pin "2") (pinfunction "2_2") (pintype "passive"))
      (node (ref "U4") (pin "40") (pinfunction "~{RESET}_40") (pintype "bidirectional"))
    )
    (net (code "10") (name "4060_CLK") (class "Default")
      (node (ref "C31") (pin "2") (pinfunction "2_2") (pintype "passive"))
      (node (ref "R16") (pin "2") (pinfunction "2_2") (pintype "passive"))
      (node (ref "R17") (pin "1") (pinfunction "1_1") (pintype "passive"))
    )
    (net (code "11") (name "CA3140-") (class "Default")
      (node (ref "C16") (pin "1") (pinfunction "1_1") (pintype "passive"))
      (node (ref "IC1") (pin "2") (pinfunction "-IN_2") (pintype "input"))
      (node (ref "R5") (pin "2") (pinfunction "S_2") (pintype "passive"))
    )
    (net (code "12") (name "CA3140REL") (class "Default")
      (node (ref "C16") (pin "2") (pinfunction "2_2") (pintype "passive"))
      (node (ref "IC1") (pin "6") (pinfunction "OUT_6") (pintype "output"))
      (node (ref "R6") (pin "2") (pinfunction "2_2") (pintype "passive"))
      (node (ref "R8") (pin "1") (pinfunction "1_1") (pintype "passive"))
    )
    (net (code "13") (name "CT1") (class "Default")
      (node (ref "IC7") (pin "1") (pinfunction "OUT_1") (pintype "output"))
      (node (ref "R19") (pin "2") (pinfunction "2_2") (pintype "passive"))
      (node (ref "X3") (pin "1") (pinfunction "1_1") (pintype "passive"))
    )
    (net (code "14") (name "CT2") (class "Default")
      (node (ref "IC7") (pin "6") (pinfunction "IN-_6") (pintype "input"))
      (node (ref "R20") (pin "1") (pinfunction "1_1") (pintype "passive"))
      (node (ref "X3") (pin "2") (pinfunction "2_2") (pintype "passive"))
    )
    (net (code "15") (name "D0") (class "Default")
      (node (ref "H_IN") (pin "16") (pinfunction "KL_16") (pintype "passive"))
      (node (ref "U4") (pin "26") (pinfunction "PA17(I2C/SER1:1+)_26") (pintype "bidirectional"))
    )
    (net (code "16") (name "D1") (class "Default")
      (node (ref "H_IN") (pin "15") (pinfunction "KL_15") (pintype "passive"))
      (node (ref "U4") (pin "25") (pinfunction "PA16(I2C/SER1:0+)_25") (pintype "bidirectional"))
    )
    (net (code "17") (name "D2") (class "Default")
      (node (ref "H_IN") (pin "14") (pinfunction "KL_14") (pintype "passive"))
      (node (ref "U4") (pin "24") (pinfunction "PA15(XOUT/SER2:3+)_24") (pintype "bidirectional"))
    )
    (net (code "18") (name "D3") (class "Default")
      (node (ref "H_IN") (pin "13") (pinfunction "KL_13") (pintype "passive"))
      (node (ref "U4") (pin "23") (pinfunction "PA14(XIN/SER2:2+)_23") (pintype "bidirectional"))
    )
    (net (code "19") (name "D4") (class "Default")
      (node (ref "H_IN") (pin "12") (pinfunction "KL_12") (pintype "passive"))
      (node (ref "U4") (pin "22") (pinfunction "PA13(I2C/SER2:1+)_22") (pintype "bidirectional"))
    )
    (net (code "20") (name "D5") (class "Default")
      (node (ref "H_IN") (pin "11") (pinfunction "KL_11") (pintype "passive"))
      (node (ref "U4") (pin "33") (pinfunction "PA24(SER3:2+)_33") (pintype "bidirectional"))
    )
    (net (code "21") (name "D6") (class "Default")
      (node (ref "H_IN") (pin "10") (pinfunction "KL_10") (pintype "passive"))
      (node (ref "U4") (pin "34") (pinfunction "PA25(SER3:3+)_34") (pintype "bidirectional"))
    )
    (net (code "22") (name "D7") (class "Default")
      (node (ref "H_IN") (pin "9") (pinfunction "KL_9") (pintype "passive"))
      (node (ref "U4") (pin "39") (pinfunction "PA27_39") (pintype "bidirectional"))
    )
    (net (code "23") (name "ECHO") (class "Default")
      (node (ref "H_IN") (pin "21") (pinfunction "KL_21") (pintype "passive"))
      (node (ref "U4") (pin "7") (pinfunction "PB08(AIN2/SER4:0/TC4:0)_7") (pintype "bidirectional"))
    )
    (net (code "24") (name "EC_OUT") (class "Default")
      (node (ref "C36") (pin "1") (pinfunction "1_1") (pintype "passive"))
      (node (ref "D3") (pin "C") (pinfunction "C_C") (pintype "passive"))
      (node (ref "R26") (pin "2") (pinfunction "2_2") (pintype "passive"))
      (node (ref "U4") (pin "11") (pinfunction "PA06(AIN6/SER0:2/TC1:0)_11") (pintype "bidirectional"))
    )
    (net (code "25") (name "GND") (class "Default")
      (node (ref "3V3") (pin "C") (pinfunction "C_C") (pintype "passive"))
      (node (ref "5V") (pin "C") (pinfunction "C_C") (pintype "passive"))
      (node (ref "C1") (pin "2") (pinfunction "2_2") (pintype "passive"))
      (node (ref "C10") (pin "1") (pinfunction "1_1") (pintype "passive"))
      (node (ref "C11") (pin "2") (pinfunction "2_2") (pintype "passive"))
      (node (ref "C13") (pin "2") (pinfunction "2_2") (pintype "passive"))
      (node (ref "C14") (pin "1") (pinfunction "1_1") (pintype "passive"))
      (node (ref "C15") (pin "1") (pinfunction "1_1") (pintype "passive"))
      (node (ref "C17") (pin "1") (pinfunction "1_1") (pintype "passive"))
      (node (ref "C18") (pin "1") (pinfunction "1_1") (pintype "passive"))
      (node (ref "C19") (pin "1") (pinfunction "1_1") (pintype "passive"))
      (node (ref "C2") (pin "2") (pinfunction "2_2") (pintype "passive"))
      (node (ref "C20") (pin "1") (pinfunction "1_1") (pintype "passive"))
      (node (ref "C21") (pin "1") (pinfunction "1_1") (pintype "passive"))
      (node (ref "C22") (pin "1") (pinfunction "1_1") (pintype "passive"))
      (node (ref "C23") (pin "2") (pinfunction "2_2") (pintype "passive"))
      (node (ref "C24") (pin "2") (pinfunction "2_2") (pintype "passive"))
      (node (ref "C25") (pin "1") (pinfunction "1_1") (pintype "passive"))
      (node (ref "C26") (pin "2") (pinfunction "2_2") (pintype "passive"))
      (node (ref "C27") (pin "1") (pinfunction "1_1") (pintype "passive"))
      (node (ref "C28") (pin "1") (pinfunction "1_1") (pintype "passive"))
      (node (ref "C29") (pin "1") (pinfunction "1_1") (pintype "passive"))
      (node (ref "C3") (pin "2") (pinfunction "2_2") (pintype "passive"))
      (node (ref "C30") (pin "1") (pinfunction "1_1") (pintype "passive"))
      (node (ref "C32") (pin "1") (pinfunction "1_1") (pintype "passive"))
      (node (ref "C33") (pin "1") (pinfunction "1_1") (pintype "passive"))
      (node (ref "C34") (pin "1") (pinfunction "1_1") (pintype "passive"))
      (node (ref "C35") (pin "1") (pinfunction "1_1") (pintype "passive"))
      (node (ref "C36") (pin "2") (pinfunction "2_2") (pintype "passive"))
      (node (ref "C37") (pin "2") (pinfunction "2_2") (pintype "passive"))
      (node (ref "C38") (pin "2") (pinfunction "2_2") (pintype "passive"))
      (node (ref "C39") (pin "2") (pinfunction "2_2") (pintype "passive"))
      (node (ref "C4") (pin "2") (pinfunction "2_2") (pintype "passive"))
      (node (ref "C40") (pin "2") (pinfunction "2_2") (pintype "passive"))
      (node (ref "C41") (pin "2") (pinfunction "2_2") (pintype "passive"))
      (node (ref "C42") (pin "2") (pinfunction "2_2") (pintype "passive"))
      (node (ref "C43") (pin "1") (pinfunction "1_1") (pintype "passive"))
      (node (ref "C44") (pin "2") (pinfunction "2_2") (pintype "passive"))
      (node (ref "C47") (pin "2") (pinfunction "2_2") (pintype "passive"))
      (node (ref "C48") (pin "1") (pinfunction "1_1") (pintype "passive"))
      (node (ref "C49") (pin "2") (pinfunction "2_2") (pintype "passive"))
      (node (ref "C5") (pin "2") (pinfunction "2_2") (pintype "passive"))
      (node (ref "C52") (pin "2") (pinfunction "2_2") (pintype "passive"))
      (node (ref "C6") (pin "2") (pinfunction "2_2") (pintype "passive"))
      (node (ref "C7") (pin "1") (pinfunction "1_1") (pintype "passive"))
      (node (ref "C8") (pin "1") (pinfunction "1_1") (pintype "passive"))
      (node (ref "C9") (pin "1") (pinfunction "1_1") (pintype "passive"))
      (node (ref "D3") (pin "A") (pinfunction "A_A") (pintype "passive"))
      (node (ref "H_IN") (pin "18") (pinfunction "KL_18") (pintype "passive"))
      (node (ref "H_IN") (pin "2") (pinfunction "KL_2") (pintype "passive"))
      (node (ref "H_IN") (pin "22") (pinfunction "KL_22") (pintype "passive"))
      (node (ref "IC2") (pin "3") (pinfunction "+IN_3") (pintype "input"))
      (node (ref "IC3") (pin "6") (pinfunction "AGND_6") (pintype "bidirectional"))
      (node (ref "IC3") (pin "8") (pinfunction "PGND_8") (pintype "bidirectional"))
      (node (ref "IC4") (pin "3") (pinfunction "GND_3") (pintype "power_in"))
      (node (ref "IC5") (pin "6") (pinfunction "AGND_6") (pintype "bidirectional"))
      (node (ref "IC5") (pin "8") (pinfunction "PGND_8") (pintype "bidirectional"))
      (node (ref "IC6") (pin "4") (pinfunction "V-_4") (pintype "power_in"))
      (node (ref "IC7") (pin "10") (pinfunction "IN+_10") (pintype "input"))
      (node (ref "IC7") (pin "3") (pinfunction "IN+_3") (pintype "input"))
      (node (ref "IC7") (pin "5") (pinfunction "IN+_5") (pintype "input"))
      (node (ref "ICSP") (pin "6") (pinfunction "6_6") (pintype "passive"))
      (node (ref "JTAG") (pin "3") (pinfunction "GND_3") (pintype "bidirectional"))
      (node (ref "JTAG") (pin "5") (pinfunction "GND_5") (pintype "bidirectional"))
      (node (ref "LORA_ICSP") (pin "2") (pinfunction "2_2") (pintype "passive"))
      (node (ref "ON") (pin "C") (pinfunction "C_C") (pintype "passive"))
      (node (ref "Q1") (pin "E") (pinfunction "E_E") (pintype "passive"))
      (node (ref "Q11") (pin "E") (pinfunction "E_E") (pintype "passive"))
      (node (ref "Q2") (pin "E") (pinfunction "E_E") (pintype "passive"))
      (node (ref "R12") (pin "2") (pinfunction "2_2") (pintype "passive"))
      (node (ref "R13") (pin "1") (pinfunction "1_1") (pintype "passive"))
      (node (ref "R29") (pin "1") (pinfunction "1_1") (pintype "passive"))
      (node (ref "R32") (pin "1") (pinfunction "1_1") (pintype "passive"))
      (node (ref "R38") (pin "2") (pinfunction "2_2") (pintype "passive"))
      (node (ref "R41") (pin "2") (pinfunction "2_2") (pintype "passive"))
      (node (ref "R43") (pin "2") (pinfunction "2_2") (pintype "passive"))
      (node (ref "R45") (pin "2") (pinfunction "2_2") (pintype "passive"))
      (node (ref "R7") (pin "1") (pinfunction "1_1") (pintype "passive"))
      (node (ref "RESET") (pin "1") (pinfunction "1_1") (pintype "passive"))
      (node (ref "SMA_GPS") (pin "GND@0") (pinfunction "GND_GND@0") (pintype "bidirectional"))
      (node (ref "SMA_GPS") (pin "GND@1") (pinfunction "GND_GND@1") (pintype "bidirectional"))
      (node (ref "SMA_GPS") (pin "GND@2") (pinfunction "GND_GND@2") (pintype "bidirectional"))
      (node (ref "SMA_GPS") (pin "GND@3") (pinfunction "GND_GND@3") (pintype "bidirectional"))
      (node (ref "TFT") (pin "4") (pinfunction "4_4") (pintype "passive"))
      (node (ref "TR1") (pin "2") (pinfunction "S_2") (pintype "passive"))
      (node (ref "TR2") (pin "2") (pinfunction "S_2") (pintype "passive"))
      (node (ref "TR3") (pin "2") (pinfunction "S_2") (pintype "passive"))
      (node (ref "TVS1") (pin "A") (pinfunction "A_A") (pintype "passive"))
      (node (ref "U1") (pin "1") (pinfunction "GND_1") (pintype "bidirectional"))
      (node (ref "U1") (pin "11") (pinfunction "GND_11") (pintype "bidirectional"))
      (node (ref "U1") (pin "20") (pinfunction "GND_20") (pintype "bidirectional"))
      (node (ref "U1") (pin "21") (pinfunction "GND_21") (pintype "bidirectional"))
      (node (ref "U1") (pin "22") (pinfunction "GND_22") (pintype "bidirectional"))
      (node (ref "U1") (pin "24") (pinfunction "GND_24") (pintype "bidirectional"))
      (node (ref "U1") (pin "25") (pinfunction "RHL_25") (pintype "bidirectional"))
      (node (ref "U1") (pin "26") (pinfunction "GND_26") (pintype "bidirectional"))
      (node (ref "U1") (pin "27") (pinfunction "GND_27") (pintype "bidirectional"))
      (node (ref "U1") (pin "28") (pinfunction "GND_28") (pintype "bidirectional"))
      (node (ref "U1") (pin "33") (pinfunction "GND_33") (pintype "bidirectional"))
      (node (ref "U1") (pin "41") (pinfunction "GND_41") (pintype "bidirectional"))
      (node (ref "U1") (pin "47") (pinfunction "GND_47") (pintype "bidirectional"))
      (node (ref "U1") (pin "8") (pinfunction "GND_8") (pintype "bidirectional"))
      (node (ref "U3") (pin "4") (pinfunction "GND_4") (pintype "power_in"))
      (node (ref "U3") (pin "9") (pinfunction "EP_9") (pintype "passive"))
      (node (ref "U4") (pin "18") (pinfunction "GND_18") (pintype "bidirectional"))
      (node (ref "U4") (pin "35") (pinfunction "GND_35") (pintype "bidirectional"))
      (node (ref "U4") (pin "42") (pinfunction "GND_42") (pintype "bidirectional"))
      (node (ref "U4") (pin "5") (pinfunction "GNDANA_5") (pintype "bidirectional"))
      (node (ref "X1") (pin "2") (pinfunction "2_2") (pintype "passive"))
      (node (ref "X2") (pin "2") (pinfunction "2_2") (pintype "passive"))
      (node (ref "X4") (pin "1") (pinfunction "1_1") (pintype "power_in"))
      (node (ref "X4") (pin "3") (pinfunction "3_3") (pintype "power_in"))
    )
    (net (code "26") (name "HREF") (class "Default")
      (node (ref "H_IN") (pin "6") (pinfunction "KL_6") (pintype "passive"))
      (node (ref "U4") (pin "29") (pinfunction "PA20(SER5:2+)_29") (pintype "bidirectional"))
    )
    (net (code "27") (name "K1_C") (class "Default")
      (node (ref "K1") (pin "P") (pinfunction "P_P") (pintype "passive"))
      (node (ref "X5") (pin "2") (pinfunction "KL_2") (pintype "passive"))
    )
    (net (code "28") (name "K1_NC") (class "Default")
      (node (ref "K1") (pin "S") (pinfunction "S_S") (pintype "passive"))
      (node (ref "X5") (pin "3") (pinfunction "KL_3") (pintype "passive"))
    )
    (net (code "29") (name "K1_NO") (class "Default")
      (node (ref "K1") (pin "O") (pinfunction "O_O") (pintype "passive"))
      (node (ref "X5") (pin "1") (pinfunction "KL_1") (pintype "passive"))
    )
    (net (code "30") (name "K2_C") (class "Default")
      (node (ref "K2") (pin "P") (pinfunction "P_P") (pintype "passive"))
      (node (ref "X6") (pin "2") (pinfunction "KL_2") (pintype "passive"))
    )
    (net (code "31") (name "K2_NC") (class "Default")
      (node (ref "K2") (pin "S") (pinfunction "S_S") (pintype "passive"))
      (node (ref "X6") (pin "3") (pinfunction "KL_3") (pintype "passive"))
    )
    (net (code "32") (name "K2_NO") (class "Default")
      (node (ref "K2") (pin "O") (pinfunction "O_O") (pintype "passive"))
      (node (ref "X6") (pin "1") (pinfunction "KL_1") (pintype "passive"))
    )
    (net (code "33") (name "K3_C") (class "Default")
      (node (ref "K3") (pin "P") (pinfunction "P_P") (pintype "passive"))
      (node (ref "X7") (pin "2") (pinfunction "KL_2") (pintype "passive"))
    )
    (net (code "34") (name "K3_NC") (class "Default")
      (node (ref "K3") (pin "S") (pinfunction "S_S") (pintype "passive"))
      (node (ref "X7") (pin "3") (pinfunction "KL_3") (pintype "passive"))
    )
    (net (code "35") (name "K3_NO") (class "Default")
      (node (ref "K3") (pin "O") (pinfunction "O_O") (pintype "passive"))
      (node (ref "X7") (pin "1") (pinfunction "KL_1") (pintype "passive"))
    )
    (net (code "36") (name "MISO") (class "Default")
      (node (ref "ICSP") (pin "1") (pinfunction "1_1") (pintype "passive"))
      (node (ref "U4") (pin "21") (pinfunction "PA12(I2C/SER2:0+)_21") (pintype "bidirectional"))
    )
    (net (code "37") (name "MOSI") (class "Default")
      (node (ref "ICSP") (pin "4") (pinfunction "4_4") (pintype "passive"))
      (node (ref "U4") (pin "19") (pinfunction "PB10(SER4:2+)_19") (pintype "bidirectional"))
    )
    (net (code "38") (name "Net-(!RESET-PadC)") (class "Default")
      (node (ref "!RESET") (pin "C") (pinfunction "C_C") (pintype "passive"))
      (node (ref "R3") (pin "2") (pinfunction "2_2") (pintype "passive"))
    )
    (net (code "39") (name "Net-(3V3-PadA)") (class "Default")
      (node (ref "3V3") (pin "A") (pinfunction "A_A") (pintype "passive"))
      (node (ref "R34") (pin "2") (pinfunction "2_2") (pintype "passive"))
    )
    (net (code "40") (name "Net-(5V-PadA)") (class "Default")
      (node (ref "5V") (pin "A") (pinfunction "A_A") (pintype "passive"))
      (node (ref "R33") (pin "2") (pinfunction "2_2") (pintype "passive"))
    )
    (net (code "41") (name "Net-(D1-PadA)") (class "Default")
      (node (ref "D1") (pin "A") (pinfunction "A_A") (pintype "passive"))
      (node (ref "R22") (pin "2") (pinfunction "2_2") (pintype "passive"))
      (node (ref "R24") (pin "1") (pinfunction "1_1") (pintype "passive"))
    )
    (net (code "42") (name "Net-(D4-PadA)") (class "Default")
      (node (ref "D4") (pin "A") (pinfunction "A_A") (pintype "passive"))
      (node (ref "K1") (pin "2") (pinfunction "2_2") (pintype "passive"))
      (node (ref "Q11") (pin "C") (pinfunction "C_C") (pintype "passive"))
    )
    (net (code "43") (name "Net-(D5-PadA)") (class "Default")
      (node (ref "D5") (pin "A") (pinfunction "A_A") (pintype "passive"))
      (node (ref "K2") (pin "2") (pinfunction "2_2") (pintype "passive"))
      (node (ref "Q1") (pin "C") (pinfunction "C_C") (pintype "passive"))
    )
    (net (code "44") (name "Net-(D6-PadC)") (class "Default")
      (node (ref "D6") (pin "C") (pinfunction "C_C") (pintype "passive"))
      (node (ref "Q1") (pin "B") (pinfunction "B_B") (pintype "passive"))
    )
    (net (code "45") (name "Net-(D7-PadA)") (class "Default")
      (node (ref "D7") (pin "A") (pinfunction "A_A") (pintype "passive"))
      (node (ref "K3") (pin "2") (pinfunction "2_2") (pintype "passive"))
      (node (ref "Q2") (pin "C") (pinfunction "C_C") (pintype "passive"))
    )
    (net (code "46") (name "Net-(D8-PadC)") (class "Default")
      (node (ref "D8") (pin "C") (pinfunction "C_C") (pintype "passive"))
      (node (ref "Q2") (pin "B") (pinfunction "B_B") (pintype "passive"))
    )
    (net (code "47") (name "Net-(D11-PadC)") (class "Default")
      (node (ref "D11") (pin "C") (pinfunction "C_C") (pintype "passive"))
      (node (ref "Q11") (pin "B") (pinfunction "B_B") (pintype "passive"))
    )
    (net (code "48") (name "Net-(IC1-+IN)") (class "Default")
      (node (ref "C11") (pin "1") (pinfunction "1_1") (pintype "passive"))
      (node (ref "IC1") (pin "3") (pinfunction "+IN_3") (pintype "input"))
      (node (ref "R4") (pin "2") (pinfunction "2_2") (pintype "passive"))
    )
    (net (code "49") (name "Net-(IC3-BOOT)") (class "Default")
      (node (ref "C45") (pin "1") (pinfunction "1_1") (pintype "passive"))
      (node (ref "IC3") (pin "2") (pinfunction "BOOT_2") (pintype "bidirectional"))
    )
    (net (code "50") (name "Net-(IC3-FB)") (class "Default")
      (node (ref "C46") (pin "1") (pinfunction "1_1") (pintype "passive"))
      (node (ref "IC3") (pin "4") (pinfunction "FB_4") (pintype "bidirectional"))
      (node (ref "R29") (pin "2") (pinfunction "2_2") (pintype "passive"))
      (node (ref "R30") (pin "1") (pinfunction "1_1") (pintype "passive"))
    )
    (net (code "51") (name "Net-(IC3-SW)") (class "Default")
      (node (ref "C45") (pin "2") (pinfunction "2_2") (pintype "passive"))
      (node (ref "IC3") (pin "1") (pinfunction "SW_1") (pintype "bidirectional"))
      (node (ref "L3") (pin "P$1") (pinfunction "1_P$1") (pintype "passive"))
    )
    (net (code "52") (name "Net-(IC3-VCC)") (class "Default")
      (node (ref "C44") (pin "1") (pinfunction "1_1") (pintype "passive"))
      (node (ref "IC3") (pin "3") (pinfunction "VCC_3") (pintype "bidirectional"))
    )
    (net (code "53") (name "Net-(IC4-CAP+)") (class "Default")
      (node (ref "C12") (pin "1") (pinfunction "1_1") (pintype "passive"))
      (node (ref "IC4") (pin "2") (pinfunction "CAP+_2") (pintype "passive"))
    )
    (net (code "54") (name "Net-(IC4-CAP-)") (class "Default")
      (node (ref "C12") (pin "2") (pinfunction "2_2") (pintype "passive"))
      (node (ref "IC4") (pin "4") (pinfunction "CAP-_4") (pintype "passive"))
    )
    (net (code "55") (name "Net-(IC5-BOOT)") (class "Default")
      (node (ref "C50") (pin "1") (pinfunction "1_1") (pintype "passive"))
      (node (ref "IC5") (pin "2") (pinfunction "BOOT_2") (pintype "bidirectional"))
    )
    (net (code "56") (name "Net-(IC5-FB)") (class "Default")
      (node (ref "C51") (pin "1") (pinfunction "1_1") (pintype "passive"))
      (node (ref "IC5") (pin "4") (pinfunction "FB_4") (pintype "bidirectional"))
      (node (ref "R31") (pin "1") (pinfunction "1_1") (pintype "passive"))
      (node (ref "R32") (pin "2") (pinfunction "2_2") (pintype "passive"))
    )
    (net (code "57") (name "Net-(IC5-SW)") (class "Default")
      (node (ref "C50") (pin "2") (pinfunction "2_2") (pintype "passive"))
      (node (ref "IC5") (pin "1") (pinfunction "SW_1") (pintype "bidirectional"))
      (node (ref "L4") (pin "P$1") (pinfunction "1_P$1") (pintype "passive"))
    )
    (net (code "58") (name "Net-(IC5-VCC)") (class "Default")
      (node (ref "C49") (pin "1") (pinfunction "1_1") (pintype "passive"))
      (node (ref "IC5") (pin "3") (pinfunction "VCC_3") (pintype "bidirectional"))
    )
    (net (code "59") (name "Net-(IC6-IN+)") (class "Default")
      (node (ref "IC6") (pin "3") (pinfunction "IN+_3") (pintype "input"))
      (node (ref "R11") (pin "1") (pinfunction "1_1") (pintype "passive"))
    )
    (net (code "60") (name "Net-(IC6-IN-)") (class "Default")
      (node (ref "IC6") (pin "2") (pinfunction "IN-_2") (pintype "input"))
      (node (ref "R13") (pin "2") (pinfunction "2_2") (pintype "passive"))
      (node (ref "R14") (pin "1") (pinfunction "1_1") (pintype "passive"))
    )
    (net (code "61") (name "Net-(IC6-OUT)") (class "Default")
      (node (ref "IC6") (pin "6") (pinfunction "OUT_6") (pintype "output"))
      (node (ref "R14") (pin "2") (pinfunction "2_2") (pintype "passive"))
      (node (ref "R15") (pin "1") (pinfunction "1_1") (pintype "passive"))
    )
    (net (code "62") (name "Net-(IC7A-IN-)") (class "Default")
      (node (ref "IC7") (pin "2") (pinfunction "IN-_2") (pintype "input"))
      (node (ref "R18") (pin "2") (pinfunction "2_2") (pintype "passive"))
      (node (ref "R19") (pin "1") (pinfunction "1_1") (pintype "passive"))
    )
    (net (code "63") (name "Net-(IC7B-OUT)") (class "Default")
      (node (ref "IC7") (pin "7") (pinfunction "OUT_7") (pintype "output"))
      (node (ref "R20") (pin "2") (pinfunction "2_2") (pintype "passive"))
      (node (ref "R21") (pin "1") (pinfunction "1_1") (pintype "passive"))
    )
    (net (code "64") (name "Net-(IC7C-IN-)") (class "Default")
      (node (ref "IC7") (pin "9") (pinfunction "IN-_9") (pintype "input"))
      (node (ref "R21") (pin "2") (pinfunction "2_2") (pintype "passive"))
      (node (ref "R22") (pin "1") (pinfunction "1_1") (pintype "passive"))
      (node (ref "R23") (pin "1") (pinfunction "1_1") (pintype "passive"))
    )
    (net (code "65") (name "Net-(IC7C-OUT)") (class "Default")
      (node (ref "D1") (pin "C") (pinfunction "C_C") (pintype "passive"))
      (node (ref "D2") (pin "A") (pinfunction "A_A") (pintype "passive"))
      (node (ref "IC7") (pin "8") (pinfunction "OUT_8") (pintype "output"))
    )
    (net (code "66") (name "Net-(IC7D-IN+)") (class "Default")
      (node (ref "D2") (pin "C") (pinfunction "C_C") (pintype "passive"))
      (node (ref "IC7") (pin "12") (pinfunction "IN+_12") (pintype "input"))
      (node (ref "R23") (pin "2") (pinfunction "2_2") (pintype "passive"))
    )
    (net (code "67") (name "Net-(IC7D-IN-)") (class "Default")
      (node (ref "IC7") (pin "13") (pinfunction "IN-_13") (pintype "input"))
      (node (ref "R24") (pin "2") (pinfunction "2_2") (pintype "passive"))
      (node (ref "R25") (pin "1") (pinfunction "1_1") (pintype "passive"))
    )
    (net (code "68") (name "Net-(IC7D-OUT)") (class "Default")
      (node (ref "IC7") (pin "14") (pinfunction "OUT_14") (pintype "output"))
      (node (ref "R25") (pin "2") (pinfunction "2_2") (pintype "passive"))
      (node (ref "R26") (pin "1") (pinfunction "1_1") (pintype "passive"))
    )
    (net (code "69") (name "Net-(IC8A-P0)") (class "Default")
      (node (ref "C31") (pin "1") (pinfunction "1_1") (pintype "passive"))
      (node (ref "IC8") (pin "9") (pinfunction "P0_9") (pintype "output"))
    )
    (net (code "70") (name "Net-(IC8A-P1)") (class "Default")
      (node (ref "IC8") (pin "11") (pinfunction "P1_11") (pintype "input"))
      (node (ref "R17") (pin "2") (pinfunction "2_2") (pintype "passive"))
    )
    (net (code "71") (name "Net-(IC8A-Q4)") (class "Default")
      (node (ref "IC8") (pin "7") (pinfunction "Q4_7") (pintype "output"))
      (node (ref "R18") (pin "1") (pinfunction "1_1") (pintype "passive"))
    )
    (net (code "72") (name "Net-(IC8A-~{P0})") (class "Default")
      (node (ref "IC8") (pin "10") (pinfunction "~{P0}_10") (pintype "output"))
      (node (ref "R16") (pin "1") (pinfunction "1_1") (pintype "passive"))
    )
    (net (code "73") (name "Net-(ON-PadA)") (class "Default")
      (node (ref "ON") (pin "A") (pinfunction "A_A") (pintype "passive"))
      (node (ref "R46") (pin "2") (pinfunction "2_2") (pintype "passive"))
    )
    (net (code "74") (name "Net-(R4-Pad1)") (class "Default")
      (node (ref "R4") (pin "1") (pinfunction "1_1") (pintype "passive"))
      (node (ref "X1") (pin "1") (pinfunction "1_1") (pintype "passive"))
    )
    (net (code "75") (name "Net-(R5-A)") (class "Default")
      (node (ref "R5") (pin "3") (pinfunction "A_3") (pintype "passive"))
      (node (ref "R7") (pin "2") (pinfunction "2_2") (pintype "passive"))
    )
    (net (code "76") (name "Net-(R5-E)") (class "Default")
      (node (ref "R5") (pin "1") (pinfunction "E_1") (pintype "passive"))
      (node (ref "R6") (pin "1") (pinfunction "1_1") (pintype "passive"))
    )
    (net (code "77") (name "Net-(R11-Pad2)") (class "Default")
      (node (ref "R11") (pin "2") (pinfunction "2_2") (pintype "passive"))
      (node (ref "R12") (pin "1") (pinfunction "1_1") (pintype "passive"))
      (node (ref "X2") (pin "1") (pinfunction "1_1") (pintype "passive"))
    )
    (net (code "78") (name "Net-(SMA_GPS-SIGNAL)") (class "Default")
      (node (ref "C41") (pin "1") (pinfunction "1_1") (pintype "passive"))
      (node (ref "L2") (pin "2") (pinfunction "2_2") (pintype "passive"))
      (node (ref "SMA_GPS") (pin "SIG") (pinfunction "SIGNAL_SIG") (pintype "bidirectional"))
    )
    (net (code "79") (name "Net-(TR1-D)") (class "Default")
      (node (ref "D6") (pin "A") (pinfunction "A_A") (pintype "passive"))
      (node (ref "R42") (pin "2") (pinfunction "2_2") (pintype "passive"))
      (node (ref "TR1") (pin "1") (pinfunction "D_1") (pintype "passive"))
    )
    (net (code "80") (name "Net-(TR2-D)") (class "Default")
      (node (ref "D8") (pin "A") (pinfunction "A_A") (pintype "passive"))
      (node (ref "R44") (pin "2") (pinfunction "2_2") (pintype "passive"))
      (node (ref "TR2") (pin "1") (pinfunction "D_1") (pintype "passive"))
    )
    (net (code "81") (name "Net-(TR3-D)") (class "Default")
      (node (ref "D11") (pin "A") (pinfunction "A_A") (pintype "passive"))
      (node (ref "R40") (pin "2") (pinfunction "2_2") (pintype "passive"))
      (node (ref "TR3") (pin "1") (pinfunction "D_1") (pintype "passive"))
    )
    (net (code "82") (name "Net-(U1-PGC_INT)") (class "Default")
      (node (ref "LORA_ICSP") (pin "5") (pinfunction "5_5") (pintype "passive"))
      (node (ref "U1") (pin "30") (pinfunction "PGC_INT_30") (pintype "bidirectional"))
    )
    (net (code "83") (name "Net-(U1-PGD_INT)") (class "Default")
      (node (ref "LORA_ICSP") (pin "4") (pinfunction "4_4") (pintype "passive"))
      (node (ref "U1") (pin "31") (pinfunction "PGD_INT_31") (pintype "bidirectional"))
    )
    (net (code "84") (name "Net-(U1-RFH)") (class "Default")
      (node (ref "C40") (pin "1") (pinfunction "1_1") (pintype "passive"))
      (node (ref "L2") (pin "1") (pinfunction "1_1") (pintype "passive"))
      (node (ref "U1") (pin "23") (pinfunction "RFH_23") (pintype "bidirectional"))
    )
    (net (code "85") (name "Net-(U1-~{RESET})") (class "Default")
      (node (ref "LORA_ICSP") (pin "1") (pinfunction "1_1") (pintype "passive"))
      (node (ref "R1") (pin "1") (pinfunction "1_1") (pintype "passive"))
      (node (ref "U1") (pin "32") (pinfunction "~{RESET}_32") (pintype "bidirectional"))
    )
    (net (code "86") (name "Net-(U4-PA00(XIN32{slash}SER1:0{slash}TC2:0))") (class "Default")
      (node (ref "C8") (pin "2") (pinfunction "2_2") (pintype "passive"))
      (node (ref "U4") (pin "1") (pinfunction "PA00(XIN32/SER1:0/TC2:0)_1") (pintype "bidirectional"))
      (node (ref "Y1") (pin "P$2") (pinfunction "2_P$2") (pintype "passive"))
    )
    (net (code "87") (name "Net-(U4-PA01(XOUT32{slash}SER1:1{slash}TC2:1))") (class "Default")
      (node (ref "C9") (pin "2") (pinfunction "2_2") (pintype "passive"))
      (node (ref "U4") (pin "2") (pinfunction "PA01(XOUT32/SER1:1/TC2:1)_2") (pintype "bidirectional"))
      (node (ref "Y1") (pin "P$1") (pinfunction "1_P$1") (pintype "passive"))
    )
    (net (code "88") (name "Net-(U4-PA03(AIN1{slash}REFA))") (class "Default")
      (node (ref "C10") (pin "2") (pinfunction "2_2") (pintype "passive"))
      (node (ref "U4") (pin "4") (pinfunction "PA03(AIN1/REFA)_4") (pintype "bidirectional"))
    )
    (net (code "89") (name "Net-(U4-PA11(AIN19{slash}SER0:3+))") (class "Default")
      (node (ref "R38") (pin "1") (pinfunction "1_1") (pintype "passive"))
      (node (ref "R39") (pin "1") (pinfunction "1_1") (pintype "passive"))
      (node (ref "U4") (pin "16") (pinfunction "PA11(AIN19/SER0:3+)_16") (pintype "bidirectional"))
    )
    (net (code "90") (name "Net-(U4-VDDANA)") (class "Default")
      (node (ref "C7") (pin "2") (pinfunction "2_2") (pintype "passive"))
      (node (ref "L1") (pin "2") (pinfunction "2_2") (pintype "passive"))
      (node (ref "U4") (pin "6") (pinfunction "VDDANA_6") (pintype "bidirectional"))
    )
    (net (code "91") (name "Net-(U4-VDDCORE)") (class "Default")
      (node (ref "C3") (pin "1") (pinfunction "1_1") (pintype "passive"))
      (node (ref "U4") (pin "43") (pinfunction "VDDCORE_43") (pintype "bidirectional"))
    )
    (net (code "92") (name "OD_OUT") (class "Default")
      (node (ref "C26") (pin "1") (pinfunction "1_1") (pintype "passive"))
      (node (ref "R15") (pin "2") (pinfunction "2_2") (pintype "passive"))
      (node (ref "U4") (pin "9") (pinfunction "PA04(AIN4/REFB/SER0:0/TC0:0)_9") (pintype "bidirectional"))
    )
    (net (code "93") (name "PCLK") (class "Default")
      (node (ref "H_IN") (pin "7") (pinfunction "KL_7") (pintype "passive"))
      (node (ref "U4") (pin "28") (pinfunction "PA19(SER1:3+)_28") (pintype "bidirectional"))
    )
    (net (code "94") (name "PH_OUT") (class "Default")
      (node (ref "IC2") (pin "6") (pinfunction "OUT_6") (pintype "output"))
      (node (ref "R10") (pin "1") (pinfunction "1_1") (pintype "passive"))
      (node (ref "U4") (pin "10") (pinfunction "PA05(AIN5/SER0:1/TC0:1)_10") (pintype "bidirectional"))
    )
    (net (code "95") (name "RELAY1") (class "Default")
      (node (ref "R41") (pin "1") (pinfunction "1_1") (pintype "passive"))
      (node (ref "TR3") (pin "3") (pinfunction "G_3") (pintype "passive"))
      (node (ref "U4") (pin "41") (pinfunction "PA28_41") (pintype "bidirectional"))
    )
    (net (code "96") (name "RELAY2") (class "Default")
      (node (ref "R43") (pin "1") (pinfunction "1_1") (pintype "passive"))
      (node (ref "TR1") (pin "3") (pinfunction "G_3") (pintype "passive"))
      (node (ref "U4") (pin "12") (pinfunction "PA07(AIN7/SER0:3/TC1:1)_12") (pintype "bidirectional"))
    )
    (net (code "97") (name "RELAY3") (class "Default")
      (node (ref "R45") (pin "1") (pinfunction "1_1") (pintype "passive"))
      (node (ref "TR2") (pin "3") (pinfunction "G_3") (pintype "passive"))
      (node (ref "U4") (pin "3") (pinfunction "PA02(AIN0/DAC)_3") (pintype "bidirectional"))
    )
    (net (code "98") (name "RES") (class "Default")
      (node (ref "TFT") (pin "3") (pinfunction "3_3") (pintype "passive"))
    )
    (net (code "99") (name "RX") (class "Default")
      (node (ref "TFT") (pin "1") (pinfunction "1_1") (pintype "passive"))
      (node (ref "U4") (pin "48") (pinfunction "PB03(AIN11/SER5:1)_48") (pintype "bidirectional"))
    )
    (net (code "100") (name "SCK") (class "Default")
      (node (ref "ICSP") (pin "3") (pinfunction "3_3") (pintype "passive"))
      (node (ref "U4") (pin "20") (pinfunction "PB11(SER4:3+)_20") (pintype "bidirectional"))
    )
    (net (code "101") (name "SCL") (class "Default")
      (node (ref "R35") (pin "2") (pinfunction "2_2") (pintype "passive"))
      (node (ref "U3") (pin "6") (pinfunction "SCL_6") (pintype "input"))
      (node (ref "U4") (pin "14") (pinfunction "PA09(I2C/AIN17/SER0:1+)_14") (pintype "bidirectional"))
    )
    (net (code "102") (name "SDA") (class "Default")
      (node (ref "R36") (pin "2") (pinfunction "2_2") (pintype "passive"))
      (node (ref "U3") (pin "5") (pinfunction "SDA_5") (pintype "bidirectional"))
      (node (ref "U4") (pin "13") (pinfunction "PA08(I2C/AIN16/SER0:0+)_13") (pintype "bidirectional"))
    )
    (net (code "103") (name "SIOC") (class "Default")
      (node (ref "H_IN") (pin "3") (pinfunction "KL_3") (pintype "passive"))
      (node (ref "R27") (pin "2") (pinfunction "2_2") (pintype "passive"))
      (node (ref "U4") (pin "32") (pinfunction "PA23(I2C/SER3:0+)_32") (pintype "bidirectional"))
    )
    (net (code "104") (name "SIOD") (class "Default")
      (node (ref "H_IN") (pin "4") (pinfunction "KL_4") (pintype "passive"))
      (node (ref "R28") (pin "2") (pinfunction "2_2") (pintype "passive"))
      (node (ref "U4") (pin "31") (pinfunction "PA22(I2C/SER3:0+)_31") (pintype "bidirectional"))
    )
    (net (code "105") (name "SWCLK") (class "Default")
      (node (ref "JTAG") (pin "4") (pinfunction "SWDCLK/TCK_4") (pintype "bidirectional"))
      (node (ref "U4") (pin "45") (pinfunction "PA30(SWCLK/SER1:2+)_45") (pintype "bidirectional"))
    )
    (net (code "106") (name "SWDIO") (class "Default")
      (node (ref "JTAG") (pin "2") (pinfunction "SWDIO/TMS_2") (pintype "bidirectional"))
      (node (ref "U4") (pin "46") (pinfunction "PA31(SWDIO/SER1:3+)_46") (pintype "bidirectional"))
    )
    (net (code "107") (name "TEMP") (class "Default")
      (node (ref "H_IN") (pin "24") (pinfunction "KL_24") (pintype "passive"))
      (node (ref "R37") (pin "1") (pinfunction "1_1") (pintype "passive"))
      (node (ref "R39") (pin "2") (pinfunction "2_2") (pintype "passive"))
    )
    (net (code "108") (name "TL081REL") (class "Default")
      (node (ref "IC2") (pin "2") (pinfunction "-IN_2") (pintype "input"))
      (node (ref "R10") (pin "2") (pinfunction "2_2") (pintype "passive"))
      (node (ref "R8") (pin "2") (pinfunction "2_2") (pintype "passive"))
      (node (ref "R9") (pin "2") (pinfunction "2_2") (pintype "passive"))
    )
    (net (code "109") (name "TRIG") (class "Default")
      (node (ref "H_IN") (pin "23") (pinfunction "KL_23") (pintype "passive"))
      (node (ref "U4") (pin "8") (pinfunction "PB09(AIN3/SER4:1/TC4:1)_8") (pintype "bidirectional"))
    )
    (net (code "110") (name "TX") (class "Default")
      (node (ref "TFT") (pin "2") (pinfunction "2_2") (pintype "passive"))
      (node (ref "U4") (pin "47") (pinfunction "PB02(AIN10/SER5:0)_47") (pintype "bidirectional"))
    )
    (net (code "111") (name "VSYNC") (class "Default")
      (node (ref "H_IN") (pin "5") (pinfunction "KL_5") (pintype "passive"))
      (node (ref "U4") (pin "30") (pinfunction "PA21(SER5:3+)_30") (pintype "bidirectional"))
    )
    (net (code "112") (name "XCLK") (class "Default")
      (node (ref "H_IN") (pin "8") (pinfunction "KL_8") (pintype "passive"))
      (node (ref "U4") (pin "27") (pinfunction "PA18(SER1:2+)_27") (pintype "bidirectional"))
    )
    (net (code "113") (name "unconnected-(H_INK-KL-Pad19)") (class "Default")
      (node (ref "H_IN") (pin "19") (pinfunction "KL_19") (pintype "passive"))
    )
    (net (code "114") (name "unconnected-(IC1-CMP-Pad8)") (class "Default")
      (node (ref "IC1") (pin "8") (pinfunction "CMP_8") (pintype "passive"))
    )
    (net (code "115") (name "unconnected-(IC1-ON-Pad5)") (class "Default")
      (node (ref "IC1") (pin "5") (pinfunction "ON_5") (pintype "passive"))
    )
    (net (code "116") (name "unconnected-(IC1-ON{slash}CMP-Pad1)") (class "Default")
      (node (ref "IC1") (pin "1") (pinfunction "ON/CMP_1") (pintype "passive"))
    )
    (net (code "117") (name "unconnected-(IC2-ON1-Pad1)") (class "Default")
      (node (ref "IC2") (pin "1") (pinfunction "ON1_1") (pintype "passive"))
    )
    (net (code "118") (name "unconnected-(IC2-ON2-Pad5)") (class "Default")
      (node (ref "IC2") (pin "5") (pinfunction "ON2_5") (pintype "passive"))
    )
    (net (code "119") (name "unconnected-(IC2-OPT-Pad8)") (class "Default")
      (node (ref "IC2") (pin "8") (pinfunction "OPT_8") (pintype "passive"))
    )
    (net (code "120") (name "unconnected-(IC4-FC-Pad1)") (class "Default")
      (node (ref "IC4") (pin "1") (pinfunction "FC_1") (pintype "open_collector"))
    )
    (net (code "121") (name "unconnected-(IC4-OSC-Pad7)") (class "Default")
      (node (ref "IC4") (pin "7") (pinfunction "OSC_7") (pintype "open_collector"))
    )
    (net (code "122") (name "unconnected-(IC8A-Q5-Pad5)") (class "Default")
      (node (ref "IC8") (pin "5") (pinfunction "Q5_5") (pintype "output"))
    )
    (net (code "123") (name "unconnected-(IC8A-Q6-Pad4)") (class "Default")
      (node (ref "IC8") (pin "4") (pinfunction "Q6_4") (pintype "output"))
    )
    (net (code "124") (name "unconnected-(IC8A-Q7-Pad6)") (class "Default")
      (node (ref "IC8") (pin "6") (pinfunction "Q7_6") (pintype "output"))
    )
    (net (code "125") (name "unconnected-(IC8A-Q8-Pad14)") (class "Default")
      (node (ref "IC8") (pin "14") (pinfunction "Q8_14") (pintype "output"))
    )
    (net (code "126") (name "unconnected-(IC8A-Q9-Pad13)") (class "Default")
      (node (ref "IC8") (pin "13") (pinfunction "Q9_13") (pintype "output"))
    )
    (net (code "127") (name "unconnected-(IC8A-Q10-Pad15)") (class "Default")
      (node (ref "IC8") (pin "15") (pinfunction "Q10_15") (pintype "output"))
    )
    (net (code "128") (name "unconnected-(IC8A-Q12-Pad1)") (class "Default")
      (node (ref "IC8") (pin "1") (pinfunction "Q12_1") (pintype "output"))
    )
    (net (code "129") (name "unconnected-(IC8A-Q13-Pad2)") (class "Default")
      (node (ref "IC8") (pin "2") (pinfunction "Q13_2") (pintype "output"))
    )
    (net (code "130") (name "unconnected-(IC8A-Q14-Pad3)") (class "Default")
      (node (ref "IC8") (pin "3") (pinfunction "Q14_3") (pintype "output"))
    )
    (net (code "131") (name "unconnected-(JTAG-GNDDTCT-Pad9)") (class "Default")
      (node (ref "JTAG") (pin "9") (pinfunction "GNDDTCT_9") (pintype "bidirectional"))
    )
    (net (code "132") (name "unconnected-(JTAG-KEY-Pad7)") (class "Default")
      (node (ref "JTAG") (pin "7") (pinfunction "KEY_7") (pintype "bidirectional"))
    )
    (net (code "133") (name "unconnected-(JTAG-NC{slash}TDI-Pad8)") (class "Default")
      (node (ref "JTAG") (pin "8") (pinfunction "NC/TDI_8") (pintype "bidirectional"))
    )
    (net (code "134") (name "unconnected-(JTAG-SWO{slash}TDO-Pad6)") (class "Default")
      (node (ref "JTAG") (pin "6") (pinfunction "SWO/TDO_6") (pintype "bidirectional"))
    )
    (net (code "135") (name "unconnected-(LORA_ICSP-Pad6)") (class "Default")
      (node (ref "LORA_ICSP") (pin "6") (pinfunction "6_6") (pintype "passive"))
    )
    (net (code "136") (name "unconnected-(U1-GPIO0-Pad35)") (class "Default")
      (node (ref "U1") (pin "35") (pinfunction "GPIO0_35") (pintype "bidirectional"))
    )
    (net (code "137") (name "unconnected-(U1-GPIO1-Pad36)") (class "Default")
      (node (ref "U1") (pin "36") (pinfunction "GPIO1_36") (pintype "bidirectional"))
    )
    (net (code "138") (name "unconnected-(U1-GPIO2-Pad37)") (class "Default")
      (node (ref "U1") (pin "37") (pinfunction "GPIO2_37") (pintype "bidirectional"))
    )
    (net (code "139") (name "unconnected-(U1-GPIO3-Pad38)") (class "Default")
      (node (ref "U1") (pin "38") (pinfunction "GPIO3_38") (pintype "bidirectional"))
    )
    (net (code "140") (name "unconnected-(U1-GPIO4-Pad39)") (class "Default")
      (node (ref "U1") (pin "39") (pinfunction "GPIO4_39") (pintype "bidirectional"))
    )
    (net (code "141") (name "unconnected-(U1-GPIO5-Pad40)") (class "Default")
      (node (ref "U1") (pin "40") (pinfunction "GPIO5_40") (pintype "bidirectional"))
    )
    (net (code "142") (name "unconnected-(U1-GPIO6-Pad43)") (class "Default")
      (node (ref "U1") (pin "43") (pinfunction "GPIO6_43") (pintype "bidirectional"))
    )
    (net (code "143") (name "unconnected-(U1-GPIO7-Pad44)") (class "Default")
      (node (ref "U1") (pin "44") (pinfunction "GPIO7_44") (pintype "bidirectional"))
    )
    (net (code "144") (name "unconnected-(U1-GPIO8-Pad45)") (class "Default")
      (node (ref "U1") (pin "45") (pinfunction "GPIO8_45") (pintype "bidirectional"))
    )
    (net (code "145") (name "unconnected-(U1-GPIO9-Pad46)") (class "Default")
      (node (ref "U1") (pin "46") (pinfunction "GPIO9_46") (pintype "bidirectional"))
    )
    (net (code "146") (name "unconnected-(U1-GPIO10-Pad14)") (class "Default")
      (node (ref "U1") (pin "14") (pinfunction "GPIO10_14") (pintype "bidirectional"))
    )
    (net (code "147") (name "unconnected-(U1-GPIO11-Pad13)") (class "Default")
      (node (ref "U1") (pin "13") (pinfunction "GPIO11_13") (pintype "bidirectional"))
    )
    (net (code "148") (name "unconnected-(U1-GPIO12-Pad10)") (class "Default")
      (node (ref "U1") (pin "10") (pinfunction "GPIO12_10") (pintype "bidirectional"))
    )
    (net (code "149") (name "unconnected-(U1-GPIO13-Pad9)") (class "Default")
      (node (ref "U1") (pin "9") (pinfunction "GPIO13_9") (pintype "bidirectional"))
    )
    (net (code "150") (name "unconnected-(U1-NC1-Pad15)") (class "Default")
      (node (ref "U1") (pin "15") (pinfunction "NC1_15") (pintype "bidirectional"))
    )
    (net (code "151") (name "unconnected-(U1-NC2-Pad16)") (class "Default")
      (node (ref "U1") (pin "16") (pinfunction "NC2_16") (pintype "bidirectional"))
    )
    (net (code "152") (name "unconnected-(U1-NC3-Pad17)") (class "Default")
      (node (ref "U1") (pin "17") (pinfunction "NC3_17") (pintype "bidirectional"))
    )
    (net (code "153") (name "unconnected-(U1-NC4-Pad18)") (class "Default")
      (node (ref "U1") (pin "18") (pinfunction "NC4_18") (pintype "bidirectional"))
    )
    (net (code "154") (name "unconnected-(U1-NC5-Pad19)") (class "Default")
      (node (ref "U1") (pin "19") (pinfunction "NC5_19") (pintype "bidirectional"))
    )
    (net (code "155") (name "unconnected-(U1-NC6-Pad29)") (class "Default")
      (node (ref "U1") (pin "29") (pinfunction "NC6_29") (pintype "bidirectional"))
    )
    (net (code "156") (name "unconnected-(U1-NC7-Pad42)") (class "Default")
      (node (ref "U1") (pin "42") (pinfunction "NC7_42") (pintype "bidirectional"))
    )
    (net (code "157") (name "unconnected-(U1-RESERVED1-Pad4)") (class "Default")
      (node (ref "U1") (pin "4") (pinfunction "RESERVED1_4") (pintype "bidirectional"))
    )
    (net (code "158") (name "unconnected-(U1-RESERVED2-Pad5)") (class "Default")
      (node (ref "U1") (pin "5") (pinfunction "RESERVED2_5") (pintype "bidirectional"))
    )
    (net (code "159") (name "unconnected-(U3B-NC-Pad1)") (class "Default")
      (node (ref "U3") (pin "1") (pinfunction "NC_1") (pintype "bidirectional"))
    )
    (net (code "160") (name "unconnected-(U3B-NC-Pad2)") (class "Default")
      (node (ref "U3") (pin "2") (pinfunction "NC_2") (pintype "bidirectional"))
    )
    (net (code "161") (name "unconnected-(U3B-NC-Pad3)") (class "Default")
      (node (ref "U3") (pin "3") (pinfunction "NC_3") (pintype "bidirectional"))
    )
    (net (code "162") (name "unconnected-(U3B-NC-Pad7)") (class "Default")
      (node (ref "U3") (pin "7") (pinfunction "NC_7") (pintype "bidirectional"))
    )
    (net (code "163") (name "unconnected-(U4-PA10(AIN18{slash}SER0:2+)-Pad15)") (class "Default")
      (node (ref "U4") (pin "15") (pinfunction "PA10(AIN18/SER0:2+)_15") (pintype "bidirectional"))
    )
  )
)
